# power.net
KiCad netlist of a schematic drawn in Altium Designer
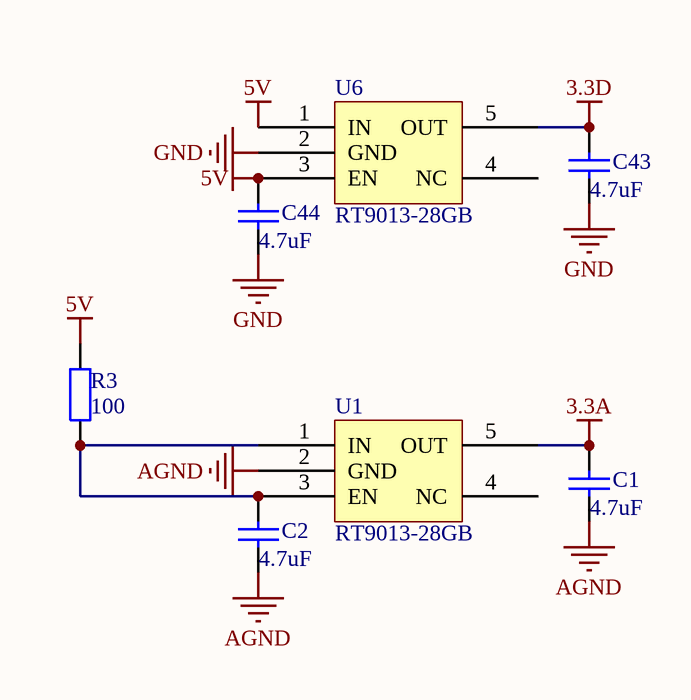
[diagram p0: power.SchDoc]

(export (version "E")
  (design (tool "Eeschema 10.0.6"))
  (components
    (comp (ref "C1")
      (value "4.7uF")
      (footprint "0603")
      (description "Capacitor")
      (fields (field (name "PUBLISHER") "Altium Limited"))
      (libsource (lib "RTC6705") (part "Cap"))
    )
    (comp (ref "C2")
      (value "4.7uF")
      (footprint "0603")
      (description "Capacitor")
      (fields (field (name "PUBLISHER") "Altium Limited"))
      (libsource (lib "RTC6705") (part "Cap"))
    )
    (comp (ref "C43")
      (value "4.7uF")
      (footprint "0603")
      (description "Capacitor")
      (fields (field (name "PUBLISHER") "Altium Limited"))
      (libsource (lib "RTC6705") (part "Cap"))
    )
    (comp (ref "C44")
      (value "4.7uF")
      (footprint "0603")
      (description "Capacitor")
      (fields (field (name "PUBLISHER") "Altium Limited"))
      (libsource (lib "RTC6705") (part "Cap"))
    )
    (comp (ref "R3")
      (value "100")
      (footprint "0603")
      (description "Resistor")
      (fields (field (name "PUBLISHER") "Altium Limited"))
      (libsource (lib "Miscellaneous Devices") (part "Res2"))
    )
    (comp (ref "U1") (value "RT9013-28GB") (footprint "SOT23-5") (libsource (lib "RTC6705") (part "LP5907")))
    (comp (ref "U6") (value "RT9013-28GB") (footprint "SOT23-5") (libsource (lib "RTC6705") (part "LP5907")))
  )
  (nets
    (net (code "1") (name "3.3A") (class "Default")
      (node (ref "C1") (pin "2") (pinfunction "2_2") (pintype "passive"))
      (node (ref "U1") (pin "5") (pinfunction "OUT_5") (pintype "passive"))
    )
    (net (code "2") (name "3.3D") (class "Default")
      (node (ref "C43") (pin "2") (pinfunction "2_2") (pintype "passive"))
      (node (ref "U6") (pin "5") (pinfunction "OUT_5") (pintype "passive"))
    )
    (net (code "3") (name "5V") (class "Default")
      (node (ref "C44") (pin "2") (pinfunction "2_2") (pintype "passive"))
      (node (ref "R3") (pin "2") (pinfunction "2_2") (pintype "passive"))
      (node (ref "U6") (pin "1") (pinfunction "IN_1") (pintype "passive"))
      (node (ref "U6") (pin "3") (pinfunction "EN_3") (pintype "passive"))
    )
    (net (code "4") (name "AGND") (class "Default")
      (node (ref "C1") (pin "1") (pinfunction "1_1") (pintype "passive"))
      (node (ref "C2") (pin "1") (pinfunction "1_1") (pintype "passive"))
      (node (ref "U1") (pin "2") (pinfunction "GND_2") (pintype "passive"))
    )
    (net (code "5") (name "GND") (class "Default")
      (node (ref "C43") (pin "1") (pinfunction "1_1") (pintype "passive"))
      (node (ref "C44") (pin "1") (pinfunction "1_1") (pintype "passive"))
      (node (ref "U6") (pin "2") (pinfunction "GND_2") (pintype "passive"))
    )
    (net (code "6") (name "Net-(U1-EN)") (class "Default")
      (node (ref "C2") (pin "2") (pinfunction "2_2") (pintype "passive"))
      (node (ref "R3") (pin "1") (pinfunction "1_1") (pintype "passive"))
      (node (ref "U1") (pin "1") (pinfunction "IN_1") (pintype "passive"))
      (node (ref "U1") (pin "3") (pinfunction "EN_3") (pintype "passive"))
    )
    (net (code "7") (name "unconnected-(U1-NC-Pad4)") (class "Default")
      (node (ref "U1") (pin "4") (pinfunction "NC_4") (pintype "passive"))
    )
    (net (code "8") (name "unconnected-(U6-NC-Pad4)") (class "Default")
      (node (ref "U6") (pin "4") (pinfunction "NC_4") (pintype "passive"))
    )
  )
)
